# -USBasp_v1_2.net
KiCad netlist of a schematic drawn in EAGLE
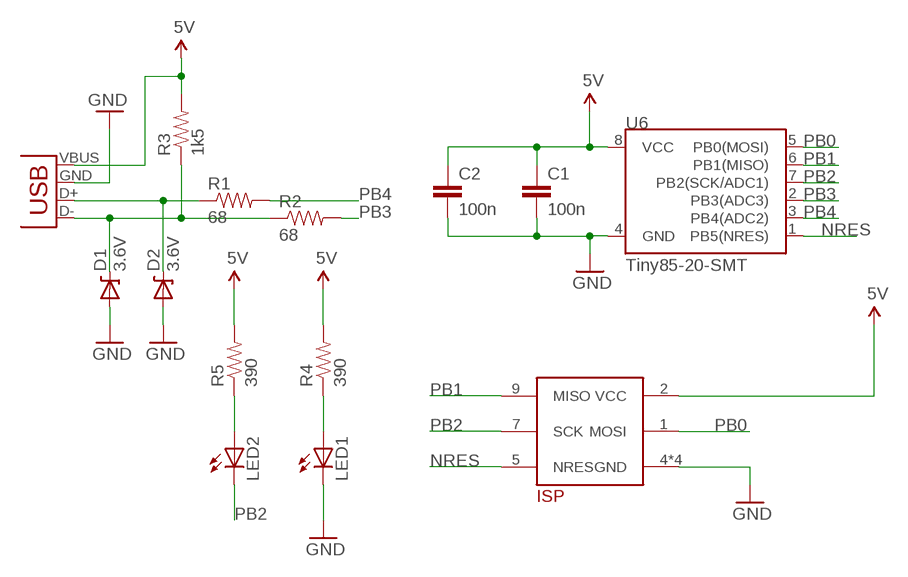
[diagram p0: schematic, sheet 1]

(export (version "E")
  (design (tool "Eeschema 10.0.6"))
  (components
    (comp (ref "C1")
      (value "100n")
      (footprint "eagle-import:0805")
      (libsource (lib "eagle-import") (part "CAP0805"))
    )
    (comp (ref "C2")
      (value "100n")
      (footprint "eagle-import:0805")
      (libsource (lib "eagle-import") (part "CAP0805"))
    )
    (comp (ref "D1")
      (value "3.6V")
      (footprint "eagle-import:SOD-323")
      (libsource (lib "eagle-import") (part "DIODE-ZENER-BZT52"))
    )
    (comp (ref "D2")
      (value "3.6V")
      (footprint "eagle-import:SOD-323")
      (libsource (lib "eagle-import") (part "DIODE-ZENER-BZT52"))
    )
    (comp (ref "JP2")
      (value "USB-A-H")
      (footprint "eagle-import:USB-A-H")
      (libsource (lib "eagle-import") (part "USB-A-H"))
    )
    (comp (ref "LED1")
      (value "LEDCHIPLED_0805")
      (footprint "eagle-import:CHIPLED_0805")
      (libsource (lib "eagle-import") (part "LEDCHIPLED_0805"))
    )
    (comp (ref "LED2")
      (value "LEDCHIPLED_0805")
      (footprint "eagle-import:CHIPLED_0805")
      (libsource (lib "eagle-import") (part "LEDCHIPLED_0805"))
    )
    (comp (ref "R1")
      (value "68")
      (footprint "eagle-import:0805")
      (libsource (lib "eagle-import") (part "RESISTOR0805-RES"))
    )
    (comp (ref "R2")
      (value "68")
      (footprint "eagle-import:0805")
      (libsource (lib "eagle-import") (part "RESISTOR0805-RES"))
    )
    (comp (ref "R3")
      (value "1k5")
      (footprint "eagle-import:0805")
      (libsource (lib "eagle-import") (part "RESISTOR0805-RES"))
    )
    (comp (ref "R4")
      (value "390")
      (footprint "eagle-import:0805")
      (libsource (lib "eagle-import") (part "RESISTOR0805-RES"))
    )
    (comp (ref "R5")
      (value "390")
      (footprint "eagle-import:0805")
      (libsource (lib "eagle-import") (part "RESISTOR0805-RES"))
    )
    (comp (ref "U$1")
      (value "TB_ISPEDGE_2X5_LONG")
      (footprint "eagle-import:ISP_EDGE2X5_LONG")
      (libsource (lib "eagle-import") (part "TB_ISPEDGE_2X5_LONG"))
    )
    (comp (ref "U6")
      (value "Tiny85-20-SMT")
      (footprint "eagle-import:SO08-EIAJ")
      (libsource (lib "eagle-import") (part "ATTINY45TINY85-20-SMT"))
    )
  )
  (nets
    (net (code "1") (name "/NRES") (class "Default")
      (node (ref "U$1") (pin "5") (pinfunction "NRES_5") (pintype "bidirectional"))
      (node (ref "U6") (pin "1") (pinfunction "PB5(NRES)_1") (pintype "bidirectional"))
    )
    (net (code "2") (name "/PB0") (class "Default")
      (node (ref "U$1") (pin "1") (pinfunction "MOSI_1") (pintype "bidirectional"))
      (node (ref "U6") (pin "5") (pinfunction "PB0(MOSI)_5") (pintype "bidirectional"))
    )
    (net (code "3") (name "/PB1") (class "Default")
      (node (ref "U$1") (pin "9") (pinfunction "MISO_9") (pintype "bidirectional"))
      (node (ref "U6") (pin "6") (pinfunction "PB1(MISO)_6") (pintype "bidirectional"))
    )
    (net (code "4") (name "/PB2") (class "Default")
      (node (ref "LED2") (pin "C") (pinfunction "C_C") (pintype "passive"))
      (node (ref "U$1") (pin "7") (pinfunction "SCK_7") (pintype "bidirectional"))
      (node (ref "U6") (pin "7") (pinfunction "PB2(SCK/ADC1)_7") (pintype "bidirectional"))
    )
    (net (code "5") (name "/PB3") (class "Default")
      (node (ref "R2") (pin "2") (pinfunction "2_2") (pintype "passive"))
      (node (ref "U6") (pin "2") (pinfunction "PB3(ADC3)_2") (pintype "bidirectional"))
    )
    (net (code "6") (name "/PB4") (class "Default")
      (node (ref "R1") (pin "2") (pinfunction "2_2") (pintype "passive"))
      (node (ref "U6") (pin "3") (pinfunction "PB4(ADC2)_3") (pintype "bidirectional"))
    )
    (net (code "7") (name "5V") (class "Default")
      (node (ref "C1") (pin "1") (pinfunction "1_1") (pintype "passive"))
      (node (ref "C2") (pin "1") (pinfunction "1_1") (pintype "passive"))
      (node (ref "JP2") (pin "VBUS") (pinfunction "GND_VBUS") (pintype "bidirectional"))
      (node (ref "R3") (pin "2") (pinfunction "2_2") (pintype "passive"))
      (node (ref "R4") (pin "2") (pinfunction "2_2") (pintype "passive"))
      (node (ref "R5") (pin "2") (pinfunction "2_2") (pintype "passive"))
      (node (ref "U$1") (pin "2") (pinfunction "VCC_2") (pintype "bidirectional"))
      (node (ref "U6") (pin "8") (pinfunction "VCC_8") (pintype "bidirectional"))
    )
    (net (code "8") (name "GND") (class "Default")
      (node (ref "C1") (pin "2") (pinfunction "2_2") (pintype "passive"))
      (node (ref "C2") (pin "2") (pinfunction "2_2") (pintype "passive"))
      (node (ref "D1") (pin "2") (pinfunction "A_2") (pintype "passive"))
      (node (ref "D2") (pin "2") (pinfunction "A_2") (pintype "passive"))
      (node (ref "JP2") (pin "GND") (pinfunction "VBUS_GND") (pintype "bidirectional"))
      (node (ref "LED1") (pin "C") (pinfunction "C_C") (pintype "passive"))
      (node (ref "U$1") (pin "10") (pinfunction "GND_10") (pintype "bidirectional"))
      (node (ref "U$1") (pin "4") (pinfunction "GND_4") (pintype "bidirectional"))
      (node (ref "U$1") (pin "6") (pinfunction "GND_6") (pintype "bidirectional"))
      (node (ref "U$1") (pin "8") (pinfunction "GND_8") (pintype "bidirectional"))
      (node (ref "U6") (pin "4") (pinfunction "GND_4") (pintype "bidirectional"))
    )
    (net (code "9") (name "Net-(D1-C)") (class "Default")
      (node (ref "D1") (pin "1") (pinfunction "C_1") (pintype "passive"))
      (node (ref "JP2") (pin "D-") (pinfunction "D+_D-") (pintype "bidirectional"))
      (node (ref "R2") (pin "1") (pinfunction "1_1") (pintype "passive"))
      (node (ref "R3") (pin "1") (pinfunction "1_1") (pintype "passive"))
    )
    (net (code "10") (name "Net-(D2-C)") (class "Default")
      (node (ref "D2") (pin "1") (pinfunction "C_1") (pintype "passive"))
      (node (ref "JP2") (pin "D+") (pinfunction "D-_D+") (pintype "bidirectional"))
      (node (ref "R1") (pin "1") (pinfunction "1_1") (pintype "passive"))
    )
    (net (code "11") (name "Net-(LED1-PadA)") (class "Default")
      (node (ref "LED1") (pin "A") (pinfunction "A_A") (pintype "passive"))
      (node (ref "R4") (pin "1") (pinfunction "1_1") (pintype "passive"))
    )
    (net (code "12") (name "Net-(LED2-PadA)") (class "Default")
      (node (ref "LED2") (pin "A") (pinfunction "A_A") (pintype "passive"))
      (node (ref "R5") (pin "1") (pinfunction "1_1") (pintype "passive"))
    )
  )
)
